# DEC9601.net
KiCad netlist of a schematic drawn in EAGLE
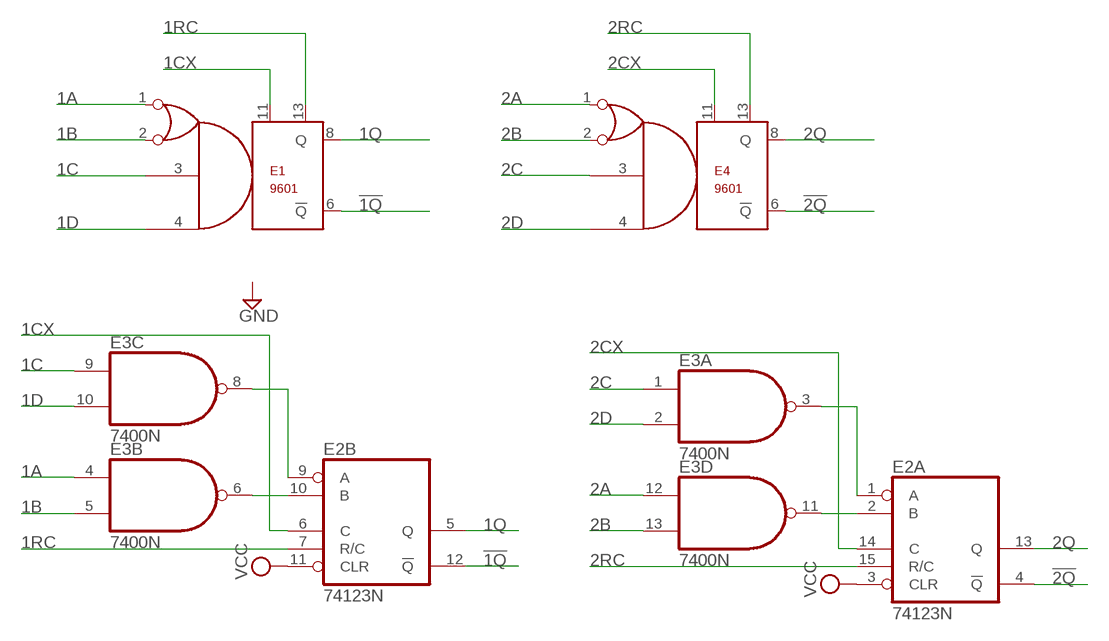
[diagram p0: schematic, sheet 1]

(export (version "E")
  (design (tool "Eeschema 10.0.6"))
  (components
    (comp (ref "E1")
      (value "9601")
      (footprint "eagle-import:DIL14")
      (libsource (lib "eagle-import") (part "9601"))
    )
    (comp (ref "E2")
      (value "74123N")
      (footprint "eagle-import:DIL16")
      (libsource (lib "eagle-import") (part "74123N"))
    )
    (comp (ref "E3")
      (value "7400N")
      (footprint "eagle-import:DIL14")
      (libsource (lib "eagle-import") (part "7400N"))
    )
    (comp (ref "E4")
      (value "9601")
      (footprint "eagle-import:DIL14")
      (libsource (lib "eagle-import") (part "9601"))
    )
  )
  (nets
    (net (code "1") (name "/1A") (class "Default")
      (node (ref "E1") (pin "1") (pinfunction "P$1_1") (pintype "input"))
      (node (ref "E3") (pin "4") (pinfunction "I0_4") (pintype "input"))
    )
    (net (code "2") (name "/1B") (class "Default")
      (node (ref "E1") (pin "2") (pinfunction "P$2_2") (pintype "input"))
      (node (ref "E3") (pin "5") (pinfunction "I1_5") (pintype "input"))
    )
    (net (code "3") (name "/1C") (class "Default")
      (node (ref "E1") (pin "3") (pinfunction "P$3_3") (pintype "input"))
      (node (ref "E3") (pin "9") (pinfunction "I0_9") (pintype "input"))
    )
    (net (code "4") (name "/1CX") (class "Default")
      (node (ref "E1") (pin "11") (pinfunction "P$5_11") (pintype "bidirectional"))
      (node (ref "E2") (pin "6") (pinfunction "C_6") (pintype "input"))
    )
    (net (code "5") (name "/1D") (class "Default")
      (node (ref "E1") (pin "4") (pinfunction "P$4_4") (pintype "input"))
      (node (ref "E3") (pin "10") (pinfunction "I1_10") (pintype "input"))
    )
    (net (code "6") (name "/1Q") (class "Default")
      (node (ref "E1") (pin "8") (pinfunction "Q_8") (pintype "output"))
      (node (ref "E2") (pin "5") (pinfunction "Q_5") (pintype "output"))
    )
    (net (code "7") (name "/1RC") (class "Default")
      (node (ref "E1") (pin "13") (pinfunction "P$6_13") (pintype "bidirectional"))
      (node (ref "E2") (pin "7") (pinfunction "R/C_7") (pintype "input"))
    )
    (net (code "8") (name "/2A") (class "Default")
      (node (ref "E3") (pin "12") (pinfunction "I0_12") (pintype "input"))
      (node (ref "E4") (pin "1") (pinfunction "P$1_1") (pintype "input"))
    )
    (net (code "9") (name "/2B") (class "Default")
      (node (ref "E3") (pin "13") (pinfunction "I1_13") (pintype "input"))
      (node (ref "E4") (pin "2") (pinfunction "P$2_2") (pintype "input"))
    )
    (net (code "10") (name "/2C") (class "Default")
      (node (ref "E3") (pin "1") (pinfunction "I0_1") (pintype "input"))
      (node (ref "E4") (pin "3") (pinfunction "P$3_3") (pintype "input"))
    )
    (net (code "11") (name "/2CX") (class "Default")
      (node (ref "E2") (pin "14") (pinfunction "C_14") (pintype "input"))
      (node (ref "E4") (pin "11") (pinfunction "P$5_11") (pintype "bidirectional"))
    )
    (net (code "12") (name "/2D") (class "Default")
      (node (ref "E3") (pin "2") (pinfunction "I1_2") (pintype "input"))
      (node (ref "E4") (pin "4") (pinfunction "P$4_4") (pintype "input"))
    )
    (net (code "13") (name "/2Q") (class "Default")
      (node (ref "E2") (pin "13") (pinfunction "Q_13") (pintype "output"))
      (node (ref "E4") (pin "8") (pinfunction "Q_8") (pintype "output"))
    )
    (net (code "14") (name "/2RC") (class "Default")
      (node (ref "E2") (pin "15") (pinfunction "R/C_15") (pintype "input"))
      (node (ref "E4") (pin "13") (pinfunction "P$6_13") (pintype "bidirectional"))
    )
    (net (code "15") (name "/~{1Q}") (class "Default")
      (node (ref "E1") (pin "6") (pinfunction "~{Q}_6") (pintype "output"))
      (node (ref "E2") (pin "12") (pinfunction "~{Q}_12") (pintype "output"))
    )
    (net (code "16") (name "/~{2Q}") (class "Default")
      (node (ref "E2") (pin "4") (pinfunction "~{Q}_4") (pintype "output"))
      (node (ref "E4") (pin "6") (pinfunction "~{Q}_6") (pintype "output"))
    )
    (net (code "18") (name "Net-(E2A-A)") (class "Default")
      (node (ref "E2") (pin "1") (pinfunction "A_1") (pintype "input"))
      (node (ref "E3") (pin "3") (pinfunction "O_3") (pintype "output"))
    )
    (net (code "19") (name "Net-(E2A-B)") (class "Default")
      (node (ref "E2") (pin "2") (pinfunction "B_2") (pintype "input"))
      (node (ref "E3") (pin "11") (pinfunction "O_11") (pintype "output"))
    )
    (net (code "20") (name "Net-(E2B-A)") (class "Default")
      (node (ref "E2") (pin "9") (pinfunction "A_9") (pintype "input"))
      (node (ref "E3") (pin "8") (pinfunction "O_8") (pintype "output"))
    )
    (net (code "21") (name "Net-(E2B-B)") (class "Default")
      (node (ref "E2") (pin "10") (pinfunction "B_10") (pintype "input"))
      (node (ref "E3") (pin "6") (pinfunction "O_6") (pintype "output"))
    )
    (net (code "22") (name "VCC") (class "Default")
      (node (ref "E2") (pin "11") (pinfunction "CLR_11") (pintype "input"))
      (node (ref "E2") (pin "3") (pinfunction "CLR_3") (pintype "input"))
    )
  )
)
